# avoccado-avr-pcb.net
KiCad netlist of a schematic drawn in EAGLE
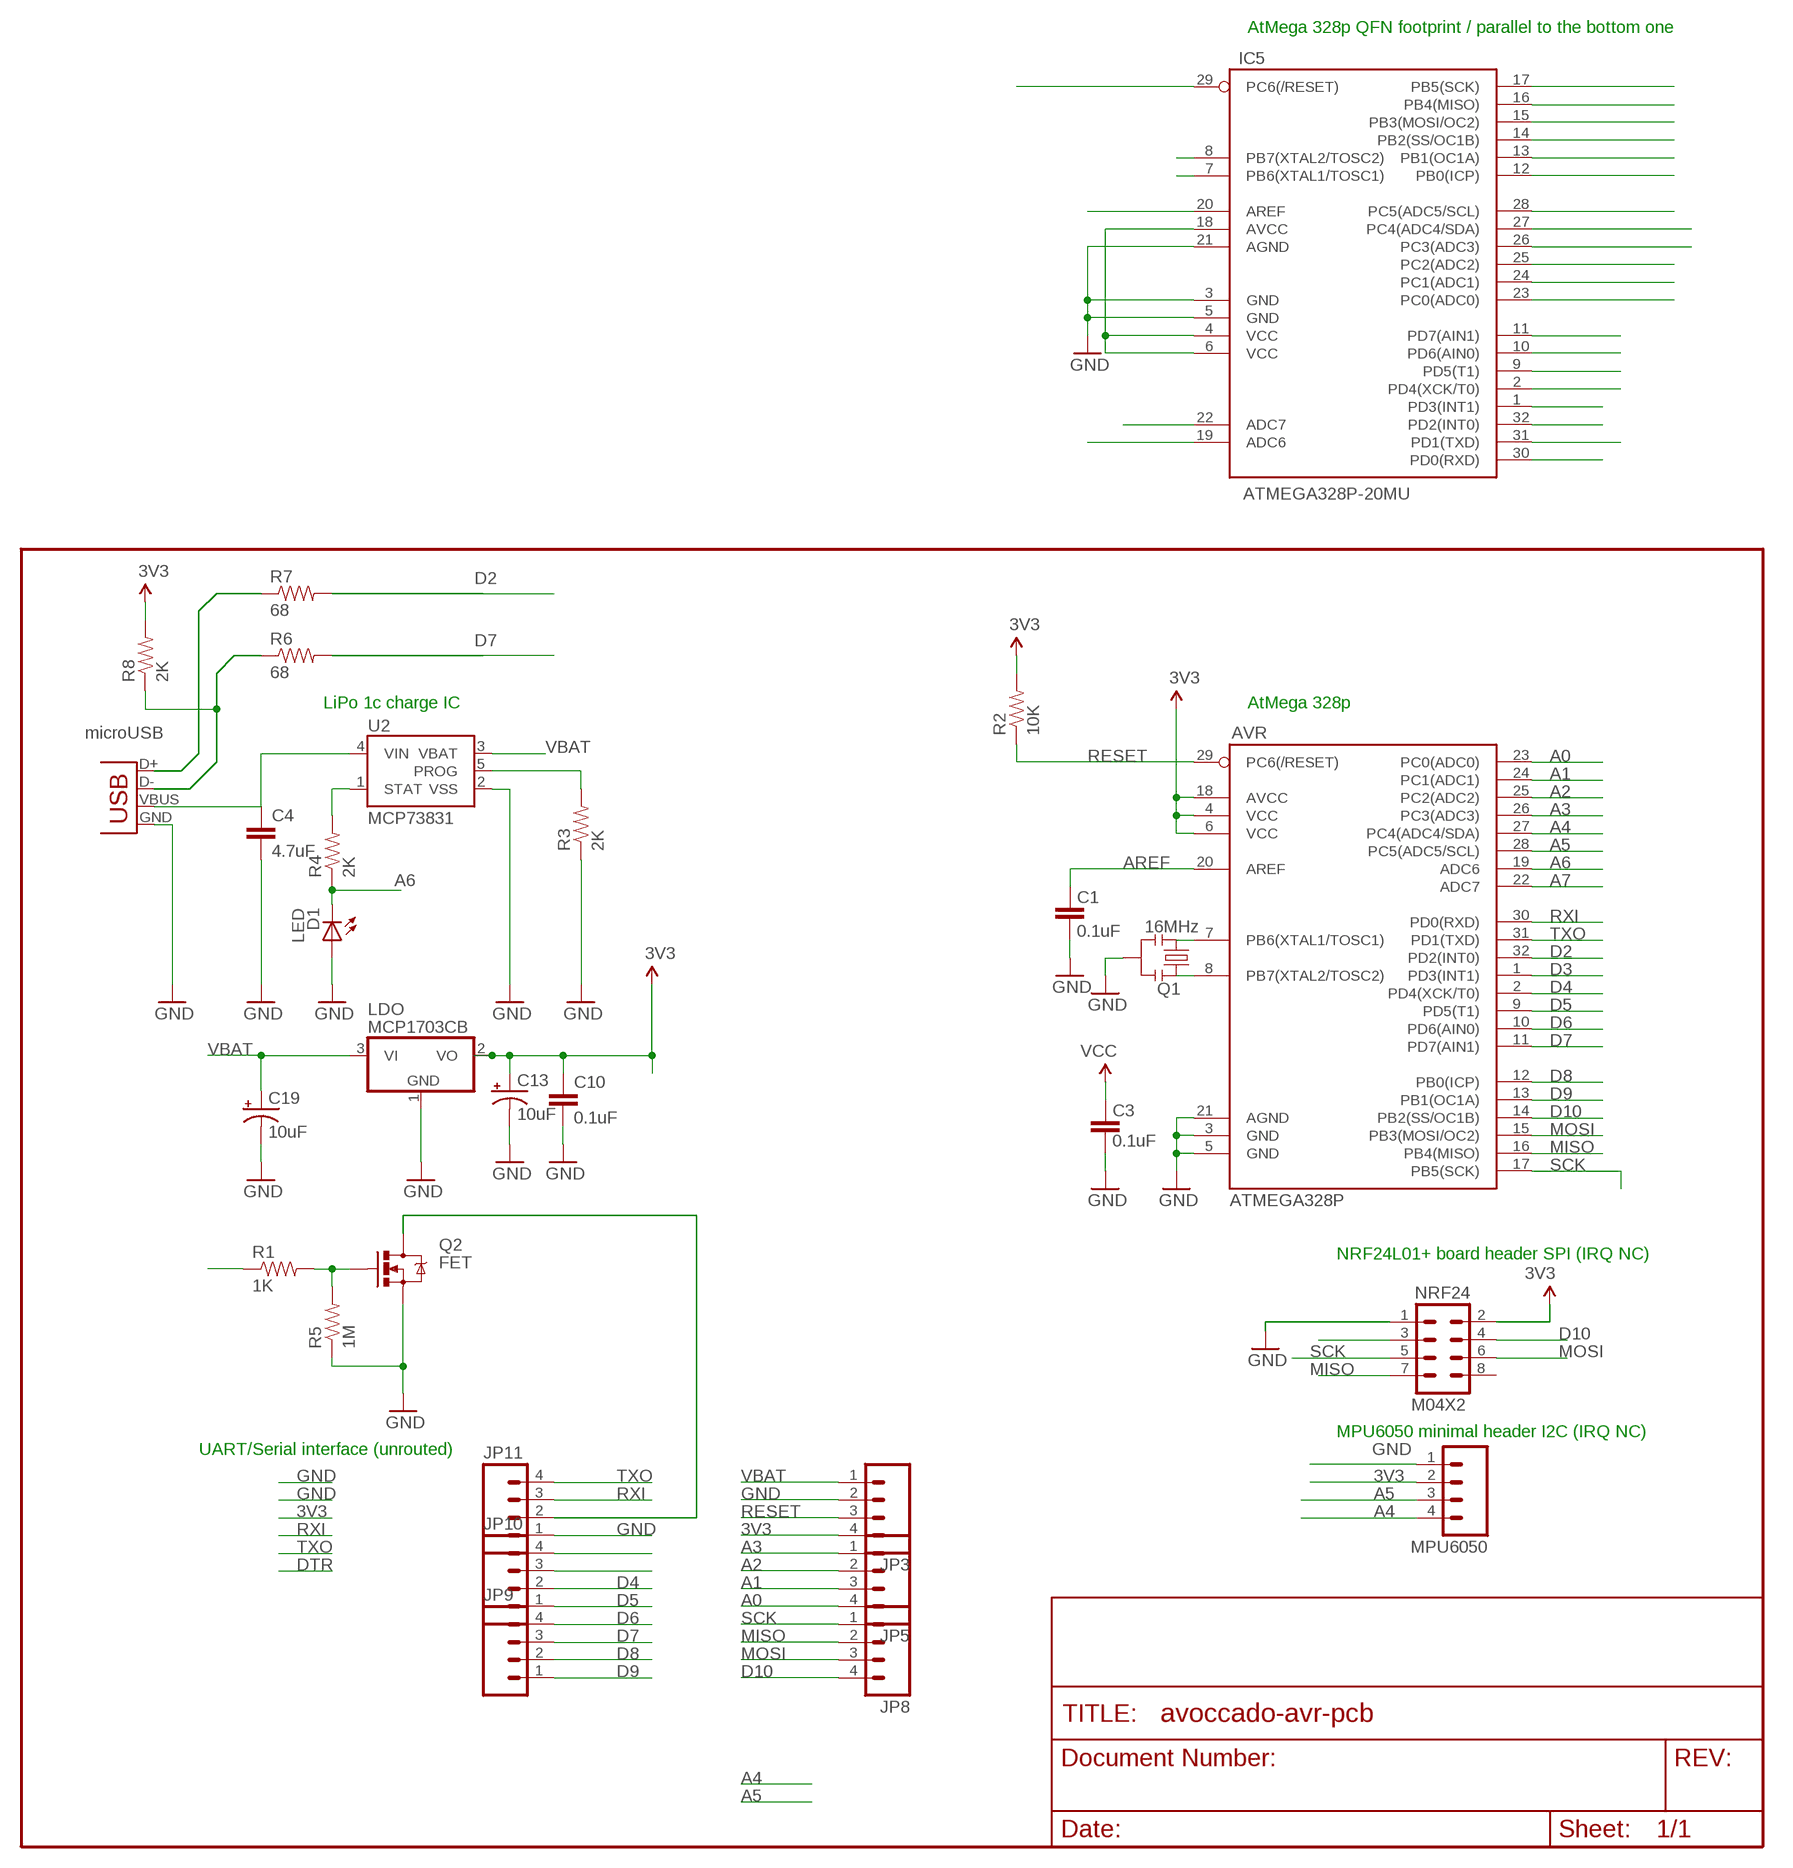
[diagram p0: schematic, sheet 1]

(export (version "E")
  (design (tool "Eeschema 10.0.6"))
  (components
    (comp (ref "AVR")
      (value "ATMEGA328P")
      (footprint "eagle-import:TQFP32-08")
      (libsource (lib "eagle-import") (part "ATMEGA328_SMT"))
    )
    (comp (ref "C1")
      (value "0.1uF")
      (footprint "eagle-import:C0402")
      (libsource (lib "eagle-import") (part "CAP0402"))
    )
    (comp (ref "C3")
      (value "0.1uF")
      (footprint "eagle-import:C0402")
      (libsource (lib "eagle-import") (part "CAP0402"))
    )
    (comp (ref "C4")
      (value "4.7uF")
      (footprint "eagle-import:0603-CAP")
      (libsource (lib "eagle-import") (part "4.7UF-6.3V-10%(0603)0603"))
    )
    (comp (ref "C10")
      (value "0.1uF")
      (footprint "eagle-import:C0402")
      (libsource (lib "eagle-import") (part "CAP0402"))
    )
    (comp (ref "C13")
      (value "10uF")
      (footprint "eagle-import:EIA3216")
      (libsource (lib "eagle-import") (part "CAP_POL1206"))
    )
    (comp (ref "C19")
      (value "10uF")
      (footprint "eagle-import:EIA3216")
      (libsource (lib "eagle-import") (part "CAP_POL1206"))
    )
    (comp (ref "D1")
      (value "LED")
      (footprint "eagle-import:LED-0603")
      (libsource (lib "eagle-import") (part "LED0603"))
    )
    (comp (ref "IC5")
      (value "ATMEGA328P-20MU")
      (footprint "eagle-import:MLF32")
      (libsource (lib "eagle-import") (part "MEGA8-MI"))
    )
    (comp (ref "JP3")
      (value "M04SMD1X4")
      (footprint "eagle-import:1X04-SMD")
      (libsource (lib "eagle-import") (part "M04SMD1X4"))
    )
    (comp (ref "JP5")
      (value "M04SMD1X4")
      (footprint "eagle-import:1X04-SMD")
      (libsource (lib "eagle-import") (part "M04SMD1X4"))
    )
    (comp (ref "JP8")
      (value "M04SMD1X4")
      (footprint "eagle-import:1X04-SMD")
      (libsource (lib "eagle-import") (part "M04SMD1X4"))
    )
    (comp (ref "JP9")
      (value "M04SMD1X4")
      (footprint "eagle-import:1X04-SMD")
      (libsource (lib "eagle-import") (part "M04SMD1X4"))
    )
    (comp (ref "JP10")
      (value "M04SMD1X4")
      (footprint "eagle-import:1X04-SMD")
      (libsource (lib "eagle-import") (part "M04SMD1X4"))
    )
    (comp (ref "JP11")
      (value "M04SMD1X4")
      (footprint "eagle-import:1X04-SMD")
      (libsource (lib "eagle-import") (part "M04SMD1X4"))
    )
    (comp (ref "LDO")
      (value "MCP1703CB")
      (footprint "eagle-import:SOT23")
      (libsource (lib "eagle-import") (part "MCP1703CB"))
    )
    (comp (ref "MPU6050")
      (value "M041X04_NO_SILK")
      (footprint "eagle-import:1X04_NO_SILK")
      (libsource (lib "eagle-import") (part "M041X04_NO_SILK"))
    )
    (comp (ref "NRF24")
      (value "M04X2")
      (footprint "eagle-import:2X4")
      (libsource (lib "eagle-import") (part "M04X2"))
    )
    (comp (ref "Q1")
      (value "16MHz")
      (footprint "eagle-import:RESONATOR-SMD")
      (libsource (lib "eagle-import") (part "RESONATORSMD"))
    )
    (comp (ref "Q2")
      (value "FET")
      (footprint "eagle-import:SOT323")
      (libsource (lib "eagle-import") (part "MOSFET-NCHANNEL2N7002PW"))
    )
    (comp (ref "R1")
      (value "1K")
      (footprint "eagle-import:0603-RES")
      (libsource (lib "eagle-import") (part "RESISTOR0603"))
    )
    (comp (ref "R2")
      (value "10K")
      (footprint "eagle-import:0603-RES")
      (libsource (lib "eagle-import") (part "RESISTOR0603"))
    )
    (comp (ref "R3")
      (value "2K")
      (footprint "eagle-import:0603-RES")
      (libsource (lib "eagle-import") (part "RESISTOR0603"))
    )
    (comp (ref "R4")
      (value "2K")
      (footprint "eagle-import:0603-RES")
      (libsource (lib "eagle-import") (part "RESISTOR0603"))
    )
    (comp (ref "R5")
      (value "1M")
      (footprint "eagle-import:0603-RES")
      (libsource (lib "eagle-import") (part "RESISTOR0603"))
    )
    (comp (ref "R6")
      (value "68")
      (footprint "eagle-import:0603-RES")
      (libsource (lib "eagle-import") (part "RESISTOR0603"))
    )
    (comp (ref "R7")
      (value "68")
      (footprint "eagle-import:0603-RES")
      (libsource (lib "eagle-import") (part "RESISTOR0603"))
    )
    (comp (ref "R8")
      (value "2K")
      (footprint "eagle-import:0603-RES")
      (libsource (lib "eagle-import") (part "RESISTOR0603"))
    )
    (comp (ref "U2")
      (value "MCP73831")
      (footprint "eagle-import:SOT23-5")
      (libsource (lib "eagle-import") (part "MCP73831"))
    )
    (comp (ref "X1")
      (value "Micro USB")
      (footprint "eagle-import:USB-MICROB")
      (libsource (lib "eagle-import") (part "USB-MICROB"))
    )
  )
  (nets
    (net (code "1") (name "/A0") (class "Default")
      (node (ref "AVR") (pin "23") (pinfunction "PC0(ADC0)_23") (pintype "bidirectional"))
      (node (ref "IC5") (pin "23") (pinfunction "PC0(ADC0)_23") (pintype "bidirectional"))
      (node (ref "JP5") (pin "4") (pinfunction "4_4") (pintype "passive"))
    )
    (net (code "2") (name "/A1") (class "Default")
      (node (ref "AVR") (pin "24") (pinfunction "PC1(ADC1)_24") (pintype "bidirectional"))
      (node (ref "IC5") (pin "24") (pinfunction "PC1(ADC1)_24") (pintype "bidirectional"))
      (node (ref "JP5") (pin "3") (pinfunction "3_3") (pintype "passive"))
    )
    (net (code "3") (name "/A2") (class "Default")
      (node (ref "AVR") (pin "25") (pinfunction "PC2(ADC2)_25") (pintype "bidirectional"))
      (node (ref "IC5") (pin "25") (pinfunction "PC2(ADC2)_25") (pintype "bidirectional"))
      (node (ref "JP5") (pin "2") (pinfunction "2_2") (pintype "passive"))
    )
    (net (code "4") (name "/A3") (class "Default")
      (node (ref "AVR") (pin "26") (pinfunction "PC3(ADC3)_26") (pintype "bidirectional"))
      (node (ref "IC5") (pin "26") (pinfunction "PC3(ADC3)_26") (pintype "bidirectional"))
      (node (ref "JP5") (pin "1") (pinfunction "1_1") (pintype "passive"))
    )
    (net (code "5") (name "/A4") (class "Default")
      (node (ref "AVR") (pin "27") (pinfunction "PC4(ADC4/SDA)_27") (pintype "bidirectional"))
      (node (ref "IC5") (pin "27") (pinfunction "PC4(ADC4/SDA)_27") (pintype "bidirectional"))
      (node (ref "MPU6050") (pin "4") (pinfunction "4_4") (pintype "passive"))
    )
    (net (code "6") (name "/A5") (class "Default")
      (node (ref "AVR") (pin "28") (pinfunction "PC5(ADC5/SCL)_28") (pintype "bidirectional"))
      (node (ref "IC5") (pin "28") (pinfunction "PC5(ADC5/SCL)_28") (pintype "bidirectional"))
      (node (ref "MPU6050") (pin "3") (pinfunction "3_3") (pintype "passive"))
    )
    (net (code "7") (name "/A6") (class "Default")
      (node (ref "AVR") (pin "19") (pinfunction "ADC6_19") (pintype "bidirectional"))
      (node (ref "D1") (pin "C") (pinfunction "C_C") (pintype "passive"))
      (node (ref "IC5") (pin "19") (pinfunction "ADC6_19") (pintype "bidirectional"))
      (node (ref "R4") (pin "1") (pinfunction "1_1") (pintype "passive"))
    )
    (net (code "8") (name "/A7") (class "Default")
      (node (ref "AVR") (pin "22") (pinfunction "ADC7_22") (pintype "bidirectional"))
      (node (ref "IC5") (pin "22") (pinfunction "ADC7_22") (pintype "bidirectional"))
    )
    (net (code "9") (name "/AREF") (class "Default")
      (node (ref "AVR") (pin "20") (pinfunction "AREF_20") (pintype "bidirectional"))
      (node (ref "C1") (pin "2") (pinfunction "2_2") (pintype "passive"))
      (node (ref "IC5") (pin "20") (pinfunction "AREF_20") (pintype "bidirectional"))
    )
    (net (code "10") (name "/D2") (class "Default")
      (node (ref "AVR") (pin "32") (pinfunction "PD2(INT0)_32") (pintype "bidirectional"))
      (node (ref "IC5") (pin "32") (pinfunction "PD2(INT0)_32") (pintype "bidirectional"))
      (node (ref "R7") (pin "2") (pinfunction "2_2") (pintype "passive"))
    )
    (net (code "11") (name "/D3") (class "Default")
      (node (ref "AVR") (pin "1") (pinfunction "PD3(INT1)_1") (pintype "bidirectional"))
      (node (ref "IC5") (pin "1") (pinfunction "PD3(INT1)_1") (pintype "bidirectional"))
      (node (ref "R1") (pin "1") (pinfunction "1_1") (pintype "passive"))
    )
    (net (code "12") (name "/D4") (class "Default")
      (node (ref "AVR") (pin "2") (pinfunction "PD4(XCK/T0)_2") (pintype "bidirectional"))
      (node (ref "IC5") (pin "2") (pinfunction "PD4(XCK/T0)_2") (pintype "bidirectional"))
      (node (ref "JP10") (pin "2") (pinfunction "2_2") (pintype "passive"))
    )
    (net (code "13") (name "/D5") (class "Default")
      (node (ref "AVR") (pin "9") (pinfunction "PD5(T1)_9") (pintype "bidirectional"))
      (node (ref "IC5") (pin "9") (pinfunction "PD5(T1)_9") (pintype "bidirectional"))
      (node (ref "JP10") (pin "1") (pinfunction "1_1") (pintype "passive"))
    )
    (net (code "14") (name "/D6") (class "Default")
      (node (ref "AVR") (pin "10") (pinfunction "PD6(AIN0)_10") (pintype "bidirectional"))
      (node (ref "IC5") (pin "10") (pinfunction "PD6(AIN0)_10") (pintype "bidirectional"))
      (node (ref "JP9") (pin "4") (pinfunction "4_4") (pintype "passive"))
    )
    (net (code "15") (name "/D7") (class "Default")
      (node (ref "AVR") (pin "11") (pinfunction "PD7(AIN1)_11") (pintype "bidirectional"))
      (node (ref "IC5") (pin "11") (pinfunction "PD7(AIN1)_11") (pintype "bidirectional"))
      (node (ref "JP9") (pin "3") (pinfunction "3_3") (pintype "passive"))
      (node (ref "R6") (pin "2") (pinfunction "2_2") (pintype "passive"))
    )
    (net (code "16") (name "/D8") (class "Default")
      (node (ref "AVR") (pin "12") (pinfunction "PB0(ICP)_12") (pintype "bidirectional"))
      (node (ref "IC5") (pin "12") (pinfunction "PB0(ICP)_12") (pintype "bidirectional"))
      (node (ref "JP9") (pin "2") (pinfunction "2_2") (pintype "passive"))
    )
    (net (code "17") (name "/D9") (class "Default")
      (node (ref "AVR") (pin "13") (pinfunction "PB1(OC1A)_13") (pintype "bidirectional"))
      (node (ref "IC5") (pin "13") (pinfunction "PB1(OC1A)_13") (pintype "bidirectional"))
      (node (ref "JP9") (pin "1") (pinfunction "1_1") (pintype "passive"))
      (node (ref "NRF24") (pin "3") (pinfunction "3_3") (pintype "passive"))
    )
    (net (code "18") (name "/D10") (class "Default")
      (node (ref "AVR") (pin "14") (pinfunction "PB2(SS/OC1B)_14") (pintype "bidirectional"))
      (node (ref "IC5") (pin "14") (pinfunction "PB2(SS/OC1B)_14") (pintype "bidirectional"))
      (node (ref "JP8") (pin "4") (pinfunction "4_4") (pintype "passive"))
      (node (ref "NRF24") (pin "4") (pinfunction "4_4") (pintype "passive"))
    )
    (net (code "20") (name "/MISO") (class "Default")
      (node (ref "AVR") (pin "16") (pinfunction "PB4(MISO)_16") (pintype "bidirectional"))
      (node (ref "IC5") (pin "16") (pinfunction "PB4(MISO)_16") (pintype "bidirectional"))
      (node (ref "JP8") (pin "2") (pinfunction "2_2") (pintype "passive"))
      (node (ref "NRF24") (pin "7") (pinfunction "7_7") (pintype "passive"))
    )
    (net (code "21") (name "/MOSI") (class "Default")
      (node (ref "AVR") (pin "15") (pinfunction "PB3(MOSI/OC2)_15") (pintype "bidirectional"))
      (node (ref "IC5") (pin "15") (pinfunction "PB3(MOSI/OC2)_15") (pintype "bidirectional"))
      (node (ref "JP8") (pin "3") (pinfunction "3_3") (pintype "passive"))
      (node (ref "NRF24") (pin "6") (pinfunction "6_6") (pintype "passive"))
    )
    (net (code "22") (name "/N$1") (class "Default")
      (node (ref "AVR") (pin "8") (pinfunction "PB7(XTAL2/TOSC2)_8") (pintype "bidirectional"))
      (node (ref "IC5") (pin "8") (pinfunction "PB7(XTAL2/TOSC2)_8") (pintype "bidirectional"))
      (node (ref "Q1") (pin "1") (pinfunction "1_1") (pintype "passive"))
    )
    (net (code "23") (name "/N$2") (class "Default")
      (node (ref "AVR") (pin "7") (pinfunction "PB6(XTAL1/TOSC1)_7") (pintype "bidirectional"))
      (node (ref "IC5") (pin "7") (pinfunction "PB6(XTAL1/TOSC1)_7") (pintype "bidirectional"))
      (node (ref "Q1") (pin "3") (pinfunction "3_3") (pintype "passive"))
    )
    (net (code "24") (name "/RESET") (class "Default")
      (node (ref "AVR") (pin "29") (pinfunction "PC6(/RESET)_29") (pintype "bidirectional"))
      (node (ref "IC5") (pin "29") (pinfunction "PC6(/RESET)_29") (pintype "bidirectional"))
      (node (ref "JP3") (pin "3") (pinfunction "3_3") (pintype "passive"))
      (node (ref "R2") (pin "1") (pinfunction "1_1") (pintype "passive"))
    )
    (net (code "25") (name "/RXI") (class "Default")
      (node (ref "AVR") (pin "30") (pinfunction "PD0(RXD)_30") (pintype "bidirectional"))
      (node (ref "IC5") (pin "30") (pinfunction "PD0(RXD)_30") (pintype "bidirectional"))
      (node (ref "JP11") (pin "3") (pinfunction "3_3") (pintype "passive"))
    )
    (net (code "26") (name "/SCK") (class "Default")
      (node (ref "AVR") (pin "17") (pinfunction "PB5(SCK)_17") (pintype "bidirectional"))
      (node (ref "IC5") (pin "17") (pinfunction "PB5(SCK)_17") (pintype "bidirectional"))
      (node (ref "JP8") (pin "1") (pinfunction "1_1") (pintype "passive"))
      (node (ref "NRF24") (pin "5") (pinfunction "5_5") (pintype "passive"))
    )
    (net (code "27") (name "/TXO") (class "Default")
      (node (ref "AVR") (pin "31") (pinfunction "PD1(TXD)_31") (pintype "bidirectional"))
      (node (ref "IC5") (pin "31") (pinfunction "PD1(TXD)_31") (pintype "bidirectional"))
      (node (ref "JP11") (pin "4") (pinfunction "4_4") (pintype "passive"))
    )
    (net (code "28") (name "/VBAT") (class "Default")
      (node (ref "C19") (pin "A") (pinfunction "+_A") (pintype "passive"))
      (node (ref "JP3") (pin "1") (pinfunction "1_1") (pintype "passive"))
      (node (ref "LDO") (pin "3") (pinfunction "VI_3") (pintype "input"))
      (node (ref "U2") (pin "3") (pinfunction "VBAT_3") (pintype "power_in"))
    )
    (net (code "29") (name "3V3") (class "Default")
      (node (ref "AVR") (pin "18") (pinfunction "AVCC_18") (pintype "bidirectional"))
      (node (ref "AVR") (pin "4") (pinfunction "VCC_4") (pintype "bidirectional"))
      (node (ref "AVR") (pin "6") (pinfunction "VCC_6") (pintype "bidirectional"))
      (node (ref "C10") (pin "1") (pinfunction "1_1") (pintype "passive"))
      (node (ref "C13") (pin "A") (pinfunction "+_A") (pintype "passive"))
      (node (ref "C3") (pin "2") (pinfunction "2_2") (pintype "passive"))
      (node (ref "IC5") (pin "18") (pinfunction "AVCC_18") (pintype "bidirectional"))
      (node (ref "IC5") (pin "4") (pinfunction "VCC_4") (pintype "bidirectional"))
      (node (ref "IC5") (pin "6") (pinfunction "VCC_6") (pintype "bidirectional"))
      (node (ref "JP3") (pin "4") (pinfunction "4_4") (pintype "passive"))
      (node (ref "LDO") (pin "2") (pinfunction "VO_2") (pintype "passive"))
      (node (ref "MPU6050") (pin "2") (pinfunction "2_2") (pintype "passive"))
      (node (ref "NRF24") (pin "2") (pinfunction "2_2") (pintype "passive"))
      (node (ref "R2") (pin "2") (pinfunction "2_2") (pintype "passive"))
      (node (ref "R8") (pin "2") (pinfunction "2_2") (pintype "passive"))
    )
    (net (code "30") (name "GND") (class "Default")
      (node (ref "AVR") (pin "21") (pinfunction "AGND_21") (pintype "bidirectional"))
      (node (ref "AVR") (pin "3") (pinfunction "GND_3") (pintype "bidirectional"))
      (node (ref "AVR") (pin "5") (pinfunction "GND_5") (pintype "bidirectional"))
      (node (ref "C1") (pin "1") (pinfunction "1_1") (pintype "passive"))
      (node (ref "C10") (pin "2") (pinfunction "2_2") (pintype "passive"))
      (node (ref "C13") (pin "C") (pinfunction "-_C") (pintype "passive"))
      (node (ref "C19") (pin "C") (pinfunction "-_C") (pintype "passive"))
      (node (ref "C3") (pin "1") (pinfunction "1_1") (pintype "passive"))
      (node (ref "C4") (pin "2") (pinfunction "2_2") (pintype "passive"))
      (node (ref "D1") (pin "A") (pinfunction "A_A") (pintype "passive"))
      (node (ref "IC5") (pin "21") (pinfunction "AGND_21") (pintype "bidirectional"))
      (node (ref "IC5") (pin "3") (pinfunction "GND_3") (pintype "bidirectional"))
      (node (ref "IC5") (pin "5") (pinfunction "GND_5") (pintype "bidirectional"))
      (node (ref "JP10") (pin "3") (pinfunction "3_3") (pintype "passive"))
      (node (ref "JP10") (pin "4") (pinfunction "4_4") (pintype "passive"))
      (node (ref "JP11") (pin "1") (pinfunction "1_1") (pintype "passive"))
      (node (ref "JP3") (pin "2") (pinfunction "2_2") (pintype "passive"))
      (node (ref "LDO") (pin "1") (pinfunction "GND_1") (pintype "passive"))
      (node (ref "MPU6050") (pin "1") (pinfunction "1_1") (pintype "passive"))
      (node (ref "NRF24") (pin "1") (pinfunction "1_1") (pintype "passive"))
      (node (ref "Q1") (pin "2") (pinfunction "2_2") (pintype "passive"))
      (node (ref "Q2") (pin "2") (pinfunction "S_2") (pintype "passive"))
      (node (ref "R3") (pin "1") (pinfunction "1_1") (pintype "passive"))
      (node (ref "R5") (pin "1") (pinfunction "1_1") (pintype "passive"))
      (node (ref "U2") (pin "2") (pinfunction "VSS_2") (pintype "power_in"))
      (node (ref "X1") (pin "GND") (pinfunction "GND_GND") (pintype "bidirectional"))
    )
    (net (code "31") (name "Net-(Q2-D)") (class "Default")
      (node (ref "JP11") (pin "2") (pinfunction "2_2") (pintype "passive"))
      (node (ref "Q2") (pin "3") (pinfunction "D_3") (pintype "passive"))
    )
    (net (code "32") (name "Net-(Q2-G)") (class "Default")
      (node (ref "Q2") (pin "1") (pinfunction "G_1") (pintype "passive"))
      (node (ref "R1") (pin "2") (pinfunction "2_2") (pintype "passive"))
      (node (ref "R5") (pin "2") (pinfunction "2_2") (pintype "passive"))
    )
    (net (code "33") (name "Net-(R6-Pad1)") (class "Default")
      (node (ref "R6") (pin "1") (pinfunction "1_1") (pintype "passive"))
      (node (ref "R8") (pin "1") (pinfunction "1_1") (pintype "passive"))
      (node (ref "X1") (pin "D-") (pinfunction "D-_D-") (pintype "bidirectional"))
    )
    (net (code "34") (name "Net-(R7-Pad1)") (class "Default")
      (node (ref "R7") (pin "1") (pinfunction "1_1") (pintype "passive"))
      (node (ref "X1") (pin "D+") (pinfunction "D+_D+") (pintype "bidirectional"))
    )
    (net (code "35") (name "Net-(U2-PROG)") (class "Default")
      (node (ref "R3") (pin "2") (pinfunction "2_2") (pintype "passive"))
      (node (ref "U2") (pin "5") (pinfunction "PROG_5") (pintype "input"))
    )
    (net (code "36") (name "Net-(U2-STAT)") (class "Default")
      (node (ref "R4") (pin "2") (pinfunction "2_2") (pintype "passive"))
      (node (ref "U2") (pin "1") (pinfunction "STAT_1") (pintype "output"))
    )
    (net (code "37") (name "Net-(U2-VIN)") (class "Default")
      (node (ref "C4") (pin "1") (pinfunction "1_1") (pintype "passive"))
      (node (ref "U2") (pin "4") (pinfunction "VIN_4") (pintype "power_in"))
      (node (ref "X1") (pin "VBUS") (pinfunction "VBUS_VBUS") (pintype "bidirectional"))
    )
    (net (code "38") (name "unconnected-(NRF24-Pad8)") (class "Default")
      (node (ref "NRF24") (pin "8") (pinfunction "8_8") (pintype "passive"))
    )
  )
)
